# LaserModule.net
KiCad netlist of a schematic drawn in EAGLE
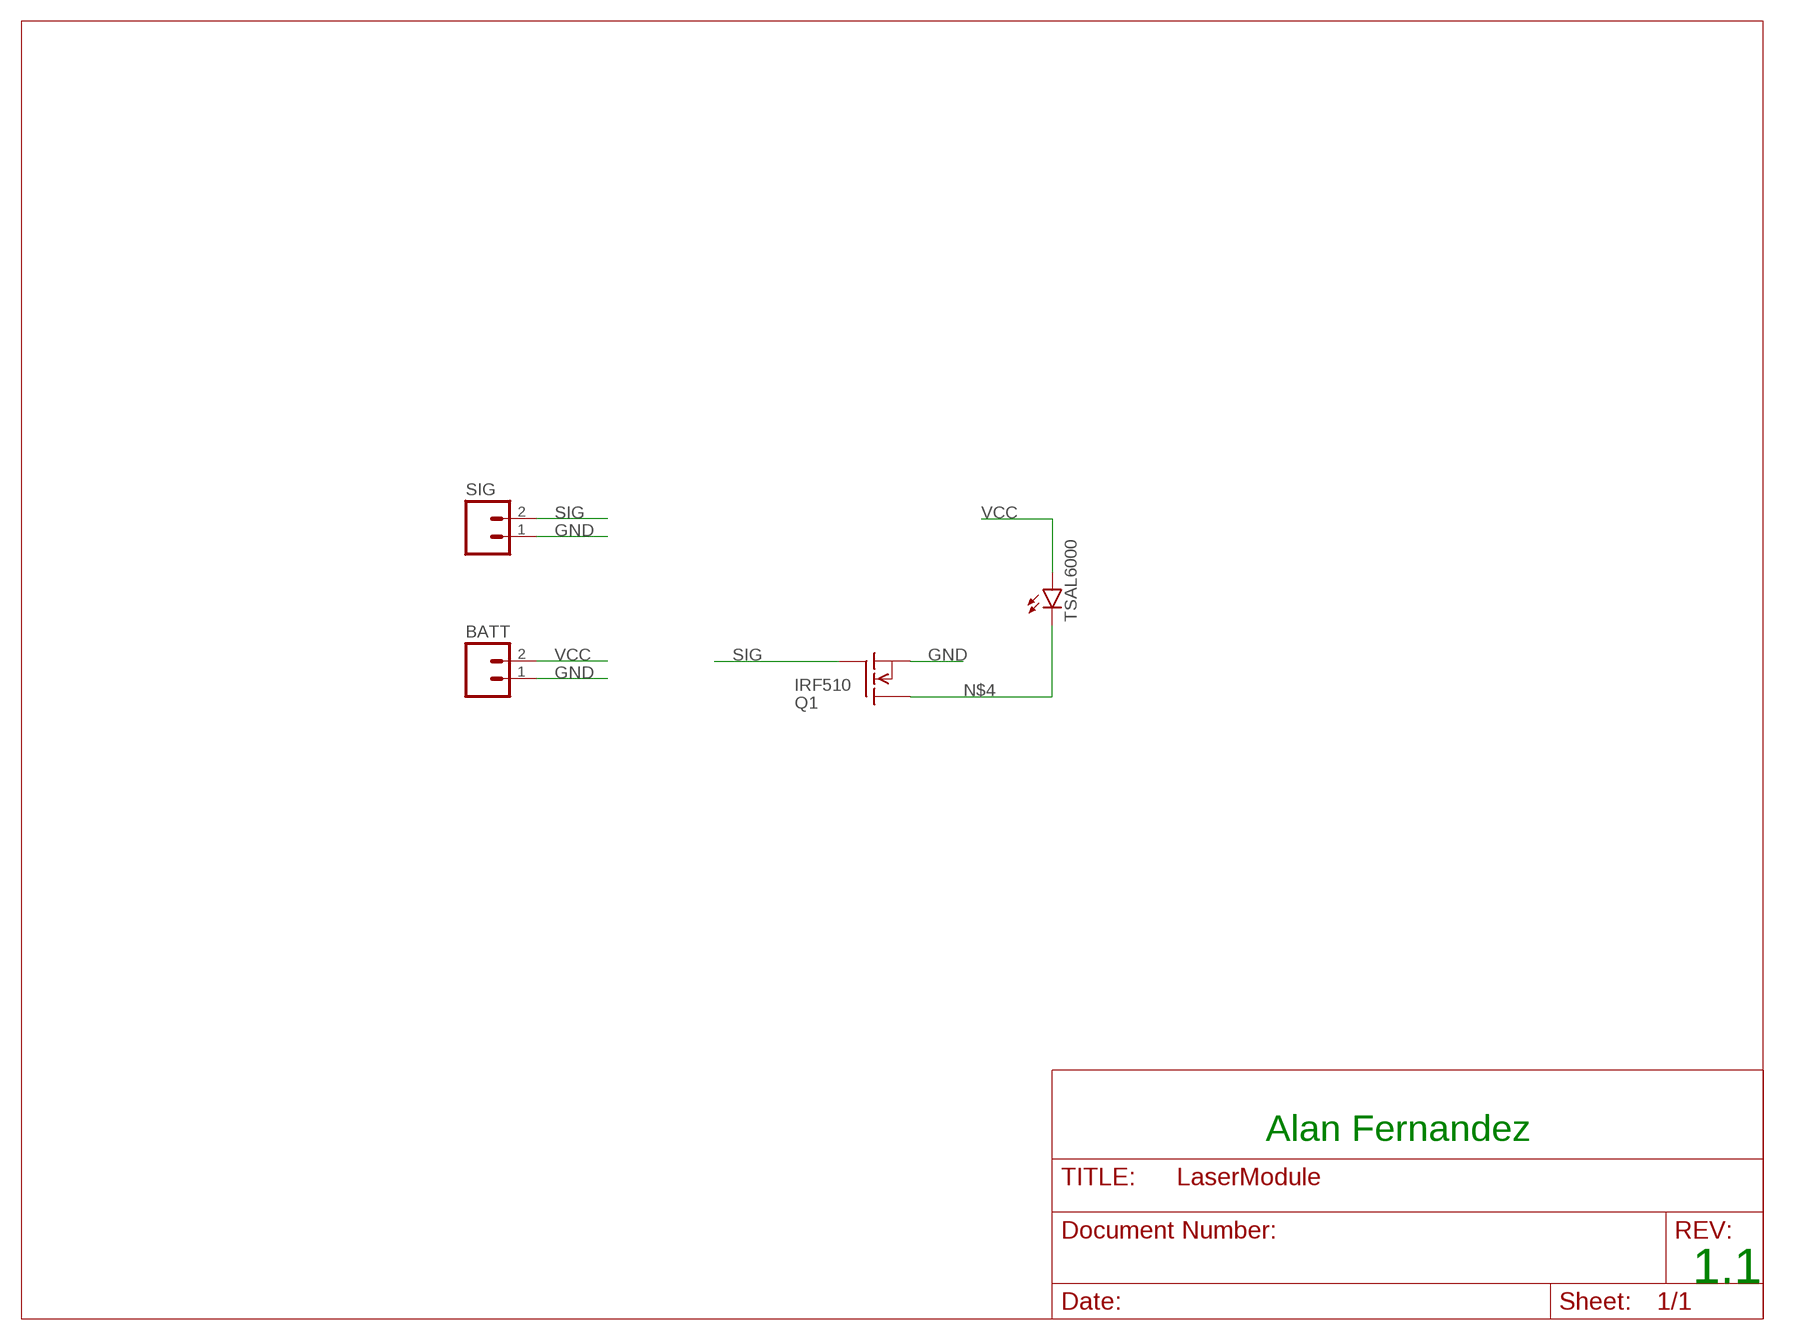
[diagram p0: schematic, sheet 1]

(export (version "E")
  (design (tool "Eeschema 10.0.6"))
  (components
    (comp (ref "BATT")
      (value "M02PTH")
      (footprint "eagle-import:1X02")
      (libsource (lib "eagle-import") (part "M02PTH"))
    )
    (comp (ref "Q1")
      (value "IRF510")
      (footprint "eagle-import:TO220")
      (libsource (lib "eagle-import") (part "IRF510"))
    )
    (comp (ref "SIG")
      (value "M02PTH")
      (footprint "eagle-import:1X02")
      (libsource (lib "eagle-import") (part "M02PTH"))
    )
    (comp (ref "TSAL6000")
      (value "LED5MM")
      (footprint "eagle-import:LED5MM")
      (libsource (lib "eagle-import") (part "LED5MM"))
    )
  )
  (nets
    (net (code "1") (name "/GND") (class "Default")
      (node (ref "BATT") (pin "1") (pinfunction "1_1") (pintype "passive"))
      (node (ref "Q1") (pin "3") (pinfunction "S_3") (pintype "passive"))
      (node (ref "SIG") (pin "1") (pinfunction "1_1") (pintype "passive"))
    )
    (net (code "2") (name "/N$4") (class "Default")
      (node (ref "Q1") (pin "2") (pinfunction "D_2") (pintype "passive"))
      (node (ref "TSAL6000") (pin "K") (pinfunction "C_K") (pintype "passive"))
    )
    (net (code "3") (name "/SIG") (class "Default")
      (node (ref "Q1") (pin "1") (pinfunction "G_1") (pintype "passive"))
      (node (ref "SIG") (pin "2") (pinfunction "2_2") (pintype "passive"))
    )
    (net (code "4") (name "/VCC") (class "Default")
      (node (ref "BATT") (pin "2") (pinfunction "2_2") (pintype "passive"))
      (node (ref "TSAL6000") (pin "A") (pinfunction "A_A") (pintype "passive"))
    )
  )
)
